# CH592F-3MODE-MS-T0-1v2.net
KiCad netlist of a schematic drawn in Altium Designer
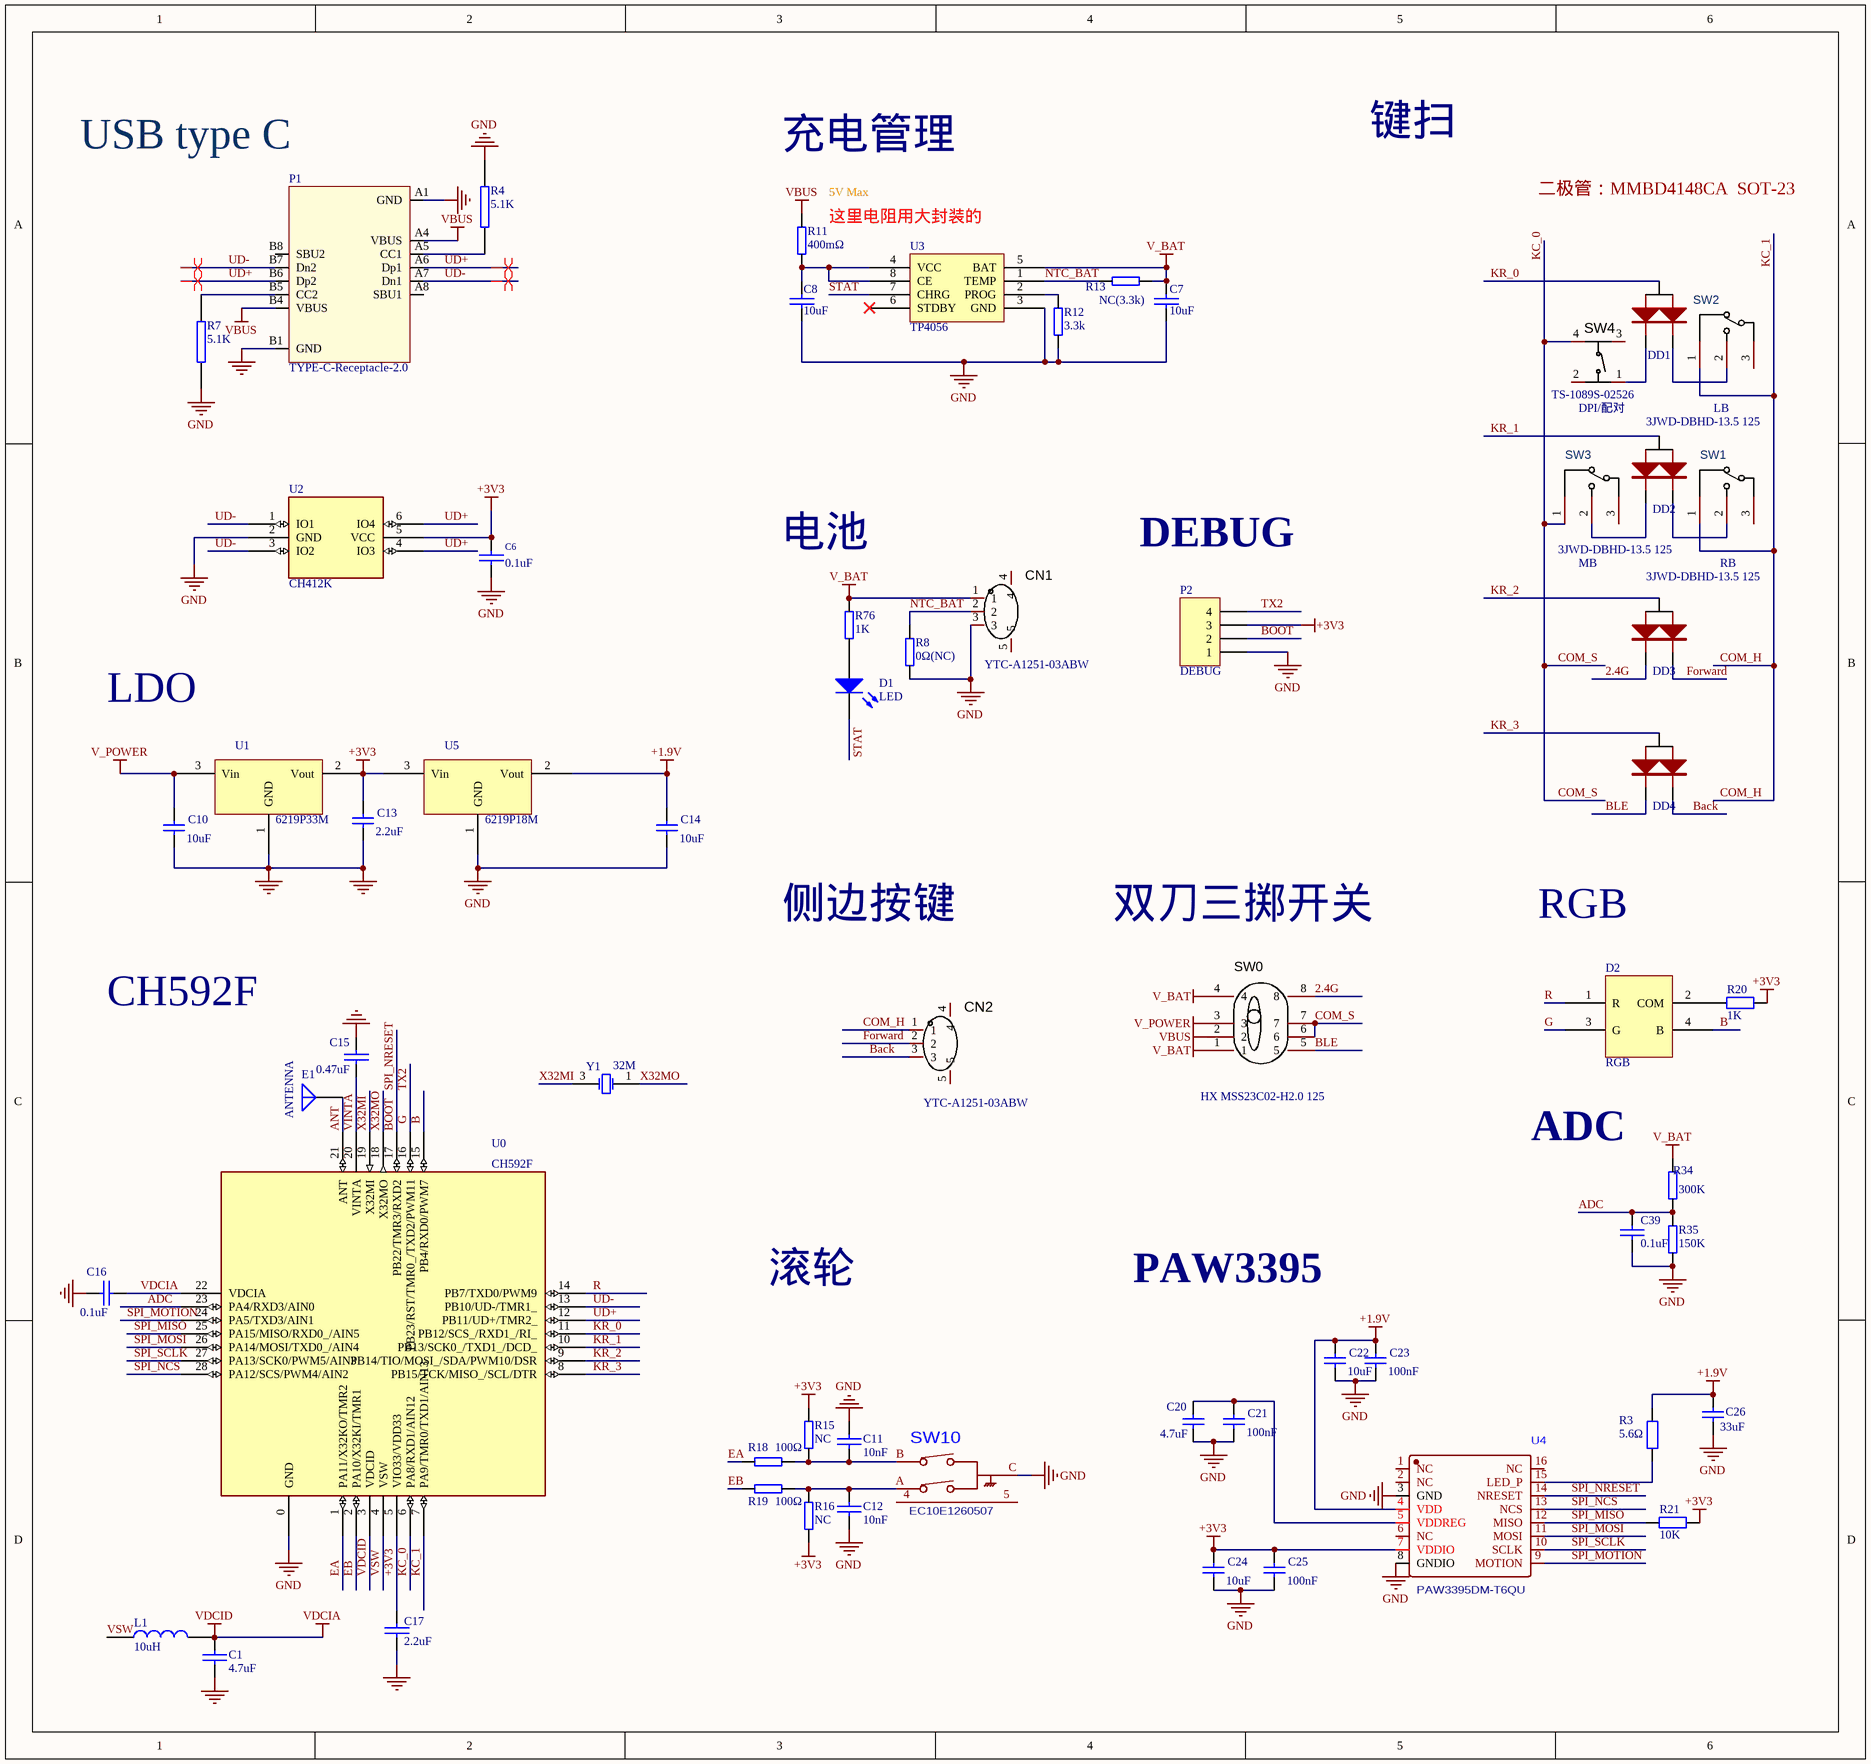
[diagram p0: CH592F-3MODE-MS-T0-1v2.SchDoc]

(export (version "E")
  (design (tool "Eeschema 10.0.6"))
  (components
    (comp (ref "C1")
      (value "4.7uF")
      (footprint "0402_C")
      (description "Capacitor")
      (libsource (lib "") (part "CAP_1"))
    )
    (comp (ref "C6")
      (value "0.1uF")
      (footprint "0402_C")
      (description "Capacitor")
      (libsource (lib "wch_sch_others") (part "CAP"))
    )
    (comp (ref "C7")
      (value "10uF")
      (footprint "0603_C")
      (description "Capacitor")
      (libsource (lib "wch_sch_others") (part "CAP"))
    )
    (comp (ref "C8")
      (value "10uF")
      (footprint "0603_C")
      (description "Capacitor")
      (libsource (lib "wch_sch_others") (part "CAP"))
    )
    (comp (ref "C10")
      (value "10uF")
      (footprint "0603_C")
      (description "Capacitor")
      (fields (field (name "PUBLISHER") "Altium Limited"))
      (libsource (lib "Miscellaneous Devices") (part "Cap"))
    )
    (comp (ref "C11")
      (value "10nF")
      (footprint "0402_C")
      (description "Capacitor")
      (libsource (lib "wch_sch_others(1)") (part "CAP"))
    )
    (comp (ref "C12")
      (value "10nF")
      (footprint "0402_C")
      (description "Capacitor")
      (libsource (lib "wch_sch_others(1)") (part "CAP"))
    )
    (comp (ref "C13")
      (value "2.2uF")
      (footprint "0402_C")
      (description "Capacitor")
      (fields (field (name "PUBLISHER") "Altium Limited"))
      (libsource (lib "Miscellaneous Devices") (part "Cap"))
    )
    (comp (ref "C14")
      (value "10uF")
      (footprint "0603_C")
      (description "Capacitor")
      (fields (field (name "PUBLISHER") "Altium Limited"))
      (libsource (lib "Miscellaneous Devices") (part "Cap"))
    )
    (comp (ref "C15")
      (value "0.47uF")
      (footprint "0402_C")
      (description "Capacitor")
      (libsource (lib "*") (part "CAP"))
    )
    (comp (ref "C16")
      (value "0.1uF")
      (footprint "0402_C")
      (description "Capacitor")
      (libsource (lib "*") (part "CAP"))
    )
    (comp (ref "C17")
      (value "2.2uF")
      (footprint "0402_C")
      (description "Capacitor")
      (libsource (lib "*") (part "CAP"))
    )
    (comp (ref "C20")
      (value "4.7uF")
      (footprint "0402_C")
      (description "Capacitor")
      (fields (field (name "PUBLISHER") "Altium Limited"))
      (libsource (lib "Miscellaneous Devices") (part "Cap"))
    )
    (comp (ref "C21")
      (value "100nF")
      (footprint "0402_C")
      (description "Capacitor")
      (fields (field (name "PUBLISHER") "Altium Limited"))
      (libsource (lib "Miscellaneous Devices") (part "Cap"))
    )
    (comp (ref "C22")
      (value "10uF")
      (footprint "0603_C")
      (description "Capacitor")
      (fields (field (name "PUBLISHER") "Altium Limited"))
      (libsource (lib "Miscellaneous Devices") (part "Cap"))
    )
    (comp (ref "C23")
      (value "100nF")
      (footprint "0402_C")
      (description "Capacitor")
      (fields (field (name "PUBLISHER") "Altium Limited"))
      (libsource (lib "Miscellaneous Devices") (part "Cap"))
    )
    (comp (ref "C24")
      (value "10uF")
      (footprint "0603_C")
      (description "Capacitor")
      (fields (field (name "PUBLISHER") "Altium Limited"))
      (libsource (lib "Miscellaneous Devices") (part "Cap"))
    )
    (comp (ref "C25")
      (value "100nF")
      (footprint "0402_C")
      (description "Capacitor")
      (fields (field (name "PUBLISHER") "Altium Limited"))
      (libsource (lib "Miscellaneous Devices") (part "Cap"))
    )
    (comp (ref "C26")
      (value "33uF")
      (footprint "3528_C")
      (description "Capacitor")
      (fields (field (name "PUBLISHER") "Altium Limited"))
      (libsource (lib "Miscellaneous Devices") (part "Cap"))
    )
    (comp (ref "C39")
      (value "0.1uF")
      (footprint "0402_C")
      (description "Capacitor")
      (libsource (lib "wch_sch_others") (part "CAP"))
    )
    (comp (ref "CN1")
      (value "YTC-A1251-03ABW")
      (footprint "CONN-SMD_3P-P1.25_YTC-A1251-03ABW")
      (fields (field (name "MANUFACTURER") "YIYUAN(怡远)"))
      (libsource (lib "altium-import") (part "root_0_YTC-A1251-03ABW_"))
    )
    (comp (ref "CN2")
      (value "YTC-A1251-03ABW")
      (footprint "CONN-SMD_3P-P1.25_YTC-A1251-03ABW")
      (fields (field (name "MANUFACTURER") "YIYUAN(怡远)"))
      (libsource (lib "altium-import") (part "root_0_YTC-A1251-03ABW_"))
    )
    (comp (ref "D1")
      (value "LED")
      (footprint "0603+")
      (description "Typical INFRARED GaAs LED")
      (fields (field (name "PUBLISHER") "Altium Limited"))
      (libsource (lib "Miscellaneous Devices") (part "LED0"))
    )
    (comp (ref "D2")
      (value "RGB")
      (footprint "RGB")
      (description "共阳")
      (libsource (lib "wch_sch_others") (part "RGB"))
    )
    (comp (ref "DD1")
      (value "DIODE")
      (footprint "CHXXX:SOT-23")
      (description "Diode")
      (libsource (lib "二极管 Copy of CH643U-White-KB-T0-1v0") (part "DIODE"))
    )
    (comp (ref "DD2")
      (value "DIODE")
      (footprint "CHXXX:SOT-23")
      (description "Diode")
      (libsource (lib "二极管 Copy of CH643U-White-KB-T0-1v0") (part "DIODE"))
    )
    (comp (ref "DD3")
      (value "DIODE")
      (footprint "CHXXX:SOT-23")
      (description "Diode")
      (libsource (lib "二极管 Copy of CH643U-White-KB-T0-1v0") (part "DIODE"))
    )
    (comp (ref "DD4")
      (value "DIODE")
      (footprint "CHXXX:SOT-23")
      (description "Diode")
      (libsource (lib "二极管 Copy of CH643U-White-KB-T0-1v0") (part "DIODE"))
    )
    (comp (ref "E1")
      (value "ANTENNA")
      (footprint "ANT-F-1-2.4G-1.0mmFR4")
      (description "Generic Antenna")
      (libsource (lib "*") (part "ANTENNA"))
    )
    (comp (ref "L1") (value "10uH") (footprint "SMD_2x2mm") (libsource (lib "*") (part "INDUCTOR")))
    (comp (ref "P1")
      (value "TYPE-C-Receptacle-2.0")
      (footprint "TYPE-C-Receptacle-2.0-6.5*8.94*3.16-SinkDown")
      (description "Type-C USB2.0 母座")
      (libsource (lib "Miscellaneous SCH Lib") (part "TYPE-C-Receptacle-2.0"))
    )
    (comp (ref "P2")
      (value "DEBUG")
      (footprint "SIP4-2.54mm")
      (description "Header, 4-Pin")
      (fields (field (name "PUBLISHER") "Altium Limited"))
      (libsource (lib "Miscellaneous Connectors") (part "Header 4"))
    )
    (comp (ref "R3")
      (value "5.6Ω")
      (footprint "0402")
      (description "Resistor")
      (fields (field (name "PUBLISHER") "Altium Limited"))
      (libsource (lib "Miscellaneous Devices") (part "Res2"))
    )
    (comp (ref "R4") (value "5.1K") (footprint "0402") (libsource (lib "*") (part "RES2")))
    (comp (ref "R7") (value "5.1K") (footprint "0402") (libsource (lib "*") (part "RES2")))
    (comp (ref "R8") (value "0Ω(NC)") (footprint "0402") (libsource (lib "wch_sch_others") (part "RES")))
    (comp (ref "R11")
      (value "400mΩ")
      (footprint "CHXXX:1206")
      (libsource (lib "wch_sch_others") (part "RES"))
    )
    (comp (ref "R12") (value "3.3k") (footprint "0402") (libsource (lib "wch_sch_others") (part "RES")))
    (comp (ref "R13") (value "NC(3.3k)") (footprint "0402") (libsource (lib "wch_sch_others") (part "RES")))
    (comp (ref "R15") (value "NC") (footprint "0402") (libsource (lib "wch_sch_others") (part "RES")))
    (comp (ref "R16") (value "NC") (footprint "0402") (libsource (lib "wch_sch_others") (part "RES")))
    (comp (ref "R18") (value "100Ω") (footprint "0402") (libsource (lib "wch_sch_others") (part "RES")))
    (comp (ref "R19") (value "100Ω") (footprint "0402") (libsource (lib "wch_sch_others") (part "RES")))
    (comp (ref "R20")
      (value "1K")
      (footprint "0402")
      (description "Resistor")
      (fields (field (name "PUBLISHER") "Altium Limited"))
      (libsource (lib "") (part "Res2_1"))
    )
    (comp (ref "R21")
      (value "10K")
      (footprint "0402")
      (description "Resistor")
      (fields (field (name "PUBLISHER") "Altium Limited"))
      (libsource (lib "") (part "Res2_1"))
    )
    (comp (ref "R34") (value "300K") (footprint "0402") (libsource (lib "wch_sch_others") (part "RES")))
    (comp (ref "R35") (value "150K") (footprint "0402") (libsource (lib "wch_sch_others") (part "RES")))
    (comp (ref "R76") (value "1K") (footprint "0402") (libsource (lib "wch_sch_others") (part "RES")))
    (comp (ref "SW0")
      (value "HX MSS23C02-H2.0 125")
      (footprint "SW-SMD_HX-MSS23C02-H2.0-125")
      (fields (field (name "MANUFACTURER") "hanxia(韩下)"))
      (libsource (lib "altium-import") (part "root_1_HX MSS23C02-H2.0 125_"))
    )
    (comp (ref "SW1")
      (value "3JWD-DBHD-13.5 125")
      (footprint "SW-TH_SHOU-HAN_3JWD-DBHD-13.5")
      (fields (field (name "MANUFACTURER") "SHOU HAN(首韩)"))
      (libsource (lib "altium-import") (part "root_0_3JWD-DBHD-13.5 125_"))
    )
    (comp (ref "SW2")
      (value "3JWD-DBHD-13.5 125")
      (footprint "SW-TH_SHOU-HAN_3JWD-DBHD-13.5")
      (fields (field (name "MANUFACTURER") "SHOU HAN(首韩)"))
      (libsource (lib "altium-import") (part "root_0_3JWD-DBHD-13.5 125_"))
    )
    (comp (ref "SW3")
      (value "3JWD-DBHD-13.5 125")
      (footprint "SW-TH_SHOU-HAN_3JWD-DBHD-13.5")
      (fields (field (name "MANUFACTURER") "SHOU HAN(首韩)"))
      (libsource (lib "altium-import") (part "root_0_3JWD-DBHD-13.5 125_"))
    )
    (comp (ref "SW4")
      (value "TS-1089S-02526")
      (footprint "SW-SMD_4P-L4.2-W3.3-P2.15-LS5.1")
      (fields (field (name "MANUFACTURER") "XUNPU(讯普)"))
      (libsource (lib "altium-import") (part "root_2_TS-1089S-02526_"))
    )
    (comp (ref "SW10")
      (value "EC10E1260507")
      (footprint "SW-TH_EC10EXXXXXXX")
      (libsource (lib "altium-import") (part "root_0_EC10E1260507_"))
    )
    (comp (ref "U0")
      (value "CH592F")
      (footprint "QFN28_4X4")
      (description "RISC-V MCU with BLE/USB/ADC/SPI/4*UART/I2C/LCD")
      (libsource (lib "DHXXXSCH") (part "CH592F"))
    )
    (comp (ref "U1")
      (value "6219P33M")
      (footprint "SOT-23")
      (libsource (lib "wch_sch_others") (part "6219P33M"))
    )
    (comp (ref "U2")
      (value "CH412K")
      (footprint "SOT-363")
      (description "Qaud ESD protect, high speed")
      (libsource (lib "CHXXX") (part "CH412K"))
    )
    (comp (ref "U3") (value "TP4056") (footprint "ESOP8") (libsource (lib "Schlib1") (part "TP4056")))
    (comp (ref "U4")
      (value "PAW3395DM-T6QU")
      (footprint "DIP-16_PAW3395DM-T6QU")
      (libsource (lib "altium-import") (part "root_0_PAW3395DM-T6QU_"))
    )
    (comp (ref "U5")
      (value "6219P18M")
      (footprint "SOT-23")
      (libsource (lib "wch_sch_others") (part "6219P33M"))
    )
    (comp (ref "Y1")
      (value "32M")
      (footprint "XT3225")
      (description "Crystal Oscillator")
      (fields (field (name "PUBLISHER") "Altium Limited"))
      (libsource (lib "*") (part "XTAL"))
    )
  )
  (nets
    (net (code "1") (name "+1.9V") (class "Default")
      (node (ref "C14") (pin "1") (pinfunction "1_1") (pintype "passive"))
      (node (ref "C22") (pin "1") (pinfunction "1_1") (pintype "passive"))
      (node (ref "C23") (pin "1") (pinfunction "1_1") (pintype "passive"))
      (node (ref "C26") (pin "1") (pinfunction "1_1") (pintype "passive"))
      (node (ref "R3") (pin "1") (pinfunction "1_1") (pintype "passive"))
      (node (ref "U4") (pin "4") (pinfunction "VDD_4") (pintype "passive"))
      (node (ref "U5") (pin "2") (pinfunction "Vout_2") (pintype "passive"))
    )
    (net (code "2") (name "+3V3") (class "Default")
      (node (ref "C13") (pin "1") (pinfunction "1_1") (pintype "passive"))
      (node (ref "C17") (pin "2") (pinfunction "2_2") (pintype "passive"))
      (node (ref "C24") (pin "1") (pinfunction "1_1") (pintype "passive"))
      (node (ref "C25") (pin "1") (pinfunction "1_1") (pintype "passive"))
      (node (ref "C6") (pin "2") (pinfunction "2_2") (pintype "passive"))
      (node (ref "P2") (pin "3") (pinfunction "3_3") (pintype "passive"))
      (node (ref "R15") (pin "2") (pintype "passive"))
      (node (ref "R16") (pin "1") (pintype "passive"))
      (node (ref "R20") (pin "1") (pinfunction "1_1") (pintype "passive"))
      (node (ref "R21") (pin "1") (pinfunction "1_1") (pintype "passive"))
      (node (ref "U0") (pin "5") (pinfunction "VIO33/VDD33_5") (pintype "power_in"))
      (node (ref "U1") (pin "2") (pinfunction "Vout_2") (pintype "passive"))
      (node (ref "U2") (pin "5") (pinfunction "VCC_5") (pintype "power_in"))
      (node (ref "U4") (pin "7") (pinfunction "VDDIO_7") (pintype "passive"))
      (node (ref "U5") (pin "3") (pinfunction "Vin_3") (pintype "passive"))
    )
    (net (code "3") (name "/2.4G") (class "Default")
      (node (ref "DD3") (pin "2") (pintype "passive"))
      (node (ref "SW0") (pin "8") (pinfunction "8_8") (pintype "passive"))
    )
    (net (code "4") (name "/ADC") (class "Default")
      (node (ref "C39") (pin "1") (pinfunction "1_1") (pintype "passive"))
      (node (ref "R34") (pin "1") (pintype "passive"))
      (node (ref "R35") (pin "2") (pintype "passive"))
      (node (ref "U0") (pin "23") (pinfunction "PA4/RXD3/AIN0_23") (pintype "bidirectional"))
    )
    (net (code "5") (name "/ANT") (class "Default")
      (node (ref "E1") (pin "1") (pinfunction "A_1") (pintype "passive"))
      (node (ref "U0") (pin "21") (pinfunction "ANT_21") (pintype "bidirectional"))
    )
    (net (code "6") (name "/B") (class "Default")
      (node (ref "D2") (pin "4") (pinfunction "B_4") (pintype "passive"))
      (node (ref "U0") (pin "15") (pinfunction "PB4/RXD0/PWM7_15") (pintype "bidirectional"))
    )
    (net (code "7") (name "/BLE") (class "Default")
      (node (ref "DD4") (pin "2") (pintype "passive"))
      (node (ref "SW0") (pin "5") (pinfunction "5_5") (pintype "passive"))
    )
    (net (code "8") (name "/BOOT") (class "Default")
      (node (ref "P2") (pin "2") (pinfunction "2_2") (pintype "passive"))
      (node (ref "U0") (pin "17") (pinfunction "PB22/TMR3/RXD2_17") (pintype "bidirectional"))
      (node (ref "U4") (pin "14") (pinfunction "NRESET_14") (pintype "passive"))
    )
    (net (code "9") (name "/Back") (class "Default")
      (node (ref "CN2") (pin "3") (pinfunction "3_3") (pintype "passive"))
      (node (ref "DD4") (pin "1") (pintype "passive"))
    )
    (net (code "10") (name "/COM_H") (class "Default")
      (node (ref "CN2") (pin "1") (pinfunction "1_1") (pintype "passive"))
      (node (ref "SW1") (pin "1") (pinfunction "C_1") (pintype "passive"))
      (node (ref "SW2") (pin "1") (pinfunction "C_1") (pintype "passive"))
      (node (ref "U0") (pin "7") (pinfunction "PA9/TMR0/TXD1/AIN13_7") (pintype "bidirectional"))
    )
    (net (code "11") (name "/COM_S") (class "Default")
      (node (ref "SW0") (pin "6") (pinfunction "6_6") (pintype "passive"))
      (node (ref "SW0") (pin "7") (pinfunction "7_7") (pintype "passive"))
      (node (ref "SW3") (pin "1") (pinfunction "C_1") (pintype "passive"))
      (node (ref "SW4") (pin "4") (pinfunction "4_4") (pintype "passive"))
      (node (ref "U0") (pin "6") (pinfunction "PA8/RXD1/AIN12_6") (pintype "bidirectional"))
    )
    (net (code "12") (name "/EA") (class "Default")
      (node (ref "R18") (pin "2") (pintype "passive"))
      (node (ref "U0") (pin "1") (pinfunction "PA11/X32KO/TMR2_1") (pintype "bidirectional"))
    )
    (net (code "13") (name "/EB") (class "Default")
      (node (ref "R19") (pin "1") (pintype "passive"))
      (node (ref "U0") (pin "2") (pinfunction "PA10/X32KI/TMR1_2") (pintype "bidirectional"))
    )
    (net (code "14") (name "/Forward") (class "Default")
      (node (ref "CN2") (pin "2") (pinfunction "2_2") (pintype "passive"))
      (node (ref "DD3") (pin "1") (pintype "passive"))
    )
    (net (code "15") (name "/G") (class "Default")
      (node (ref "D2") (pin "3") (pinfunction "G_3") (pintype "passive"))
      (node (ref "P2") (pin "4") (pinfunction "4_4") (pintype "passive"))
      (node (ref "U0") (pin "16") (pinfunction "PB23/RST/TMR0_/TXD2/PWM11_16") (pintype "bidirectional"))
    )
    (net (code "16") (name "/KR_0") (class "Default")
      (node (ref "DD1") (pin "3") (pintype "passive"))
      (node (ref "U0") (pin "11") (pinfunction "PB12/SCS_/RXD1_/RI__11") (pintype "bidirectional"))
    )
    (net (code "17") (name "/KR_1") (class "Default")
      (node (ref "DD2") (pin "3") (pintype "passive"))
      (node (ref "U0") (pin "10") (pinfunction "PB13/SCK0_/TXD1_/DCD__10") (pintype "bidirectional"))
    )
    (net (code "18") (name "/KR_2") (class "Default")
      (node (ref "DD3") (pin "3") (pintype "passive"))
      (node (ref "U0") (pin "9") (pinfunction "PB14/TIO/MOSI_/SDA/PWM10/DSR_9") (pintype "bidirectional"))
    )
    (net (code "19") (name "/KR_3") (class "Default")
      (node (ref "DD4") (pin "3") (pintype "passive"))
      (node (ref "U0") (pin "8") (pinfunction "PB15/TCK/MISO_/SCL/DTR_8") (pintype "bidirectional"))
    )
    (net (code "20") (name "/NTC_BAT") (class "Default")
      (node (ref "CN1") (pin "2") (pinfunction "2_2") (pintype "passive"))
      (node (ref "R13") (pin "2") (pintype "passive"))
      (node (ref "R8") (pin "1") (pintype "passive"))
      (node (ref "U3") (pin "1") (pinfunction "TEMP_1") (pintype "passive"))
    )
    (net (code "21") (name "/R") (class "Default")
      (node (ref "D2") (pin "1") (pinfunction "R_1") (pintype "passive"))
      (node (ref "U0") (pin "14") (pinfunction "PB7/TXD0/PWM9_14") (pintype "bidirectional"))
    )
    (net (code "22") (name "/SPI_MISO") (class "Default")
      (node (ref "R21") (pin "2") (pinfunction "2_2") (pintype "passive"))
      (node (ref "U0") (pin "25") (pinfunction "PA15/MISO/RXD0_/AIN5_25") (pintype "bidirectional"))
      (node (ref "U4") (pin "12") (pinfunction "MISO_12") (pintype "passive"))
    )
    (net (code "23") (name "/SPI_MOSI") (class "Default")
      (node (ref "U0") (pin "26") (pinfunction "PA14/MOSI/TXD0_/AIN4_26") (pintype "bidirectional"))
      (node (ref "U4") (pin "11") (pinfunction "MOSI_11") (pintype "passive"))
    )
    (net (code "24") (name "/SPI_MOTION") (class "Default")
      (node (ref "U0") (pin "24") (pinfunction "PA5/TXD3/AIN1_24") (pintype "bidirectional"))
      (node (ref "U4") (pin "9") (pinfunction "MOTION_9") (pintype "passive"))
    )
    (net (code "25") (name "/SPI_NCS") (class "Default")
      (node (ref "U0") (pin "28") (pinfunction "PA12/SCS/PWM4/AIN2_28") (pintype "bidirectional"))
      (node (ref "U4") (pin "13") (pinfunction "NCS_13") (pintype "passive"))
    )
    (net (code "26") (name "/SPI_SCLK") (class "Default")
      (node (ref "U0") (pin "27") (pinfunction "PA13/SCK0/PWM5/AIN3_27") (pintype "bidirectional"))
      (node (ref "U4") (pin "10") (pinfunction "SCLK_10") (pintype "passive"))
    )
    (net (code "27") (name "/STAT") (class "Default")
      (node (ref "D1") (pin "2") (pinfunction "K_2") (pintype "passive"))
      (node (ref "U3") (pin "7") (pinfunction "CHRG_7") (pintype "passive"))
    )
    (net (code "28") (name "/UD+") (class "Default")
      (node (ref "P1") (pin "A6") (pinfunction "Dp1_A6") (pintype "passive"))
      (node (ref "P1") (pin "B6") (pinfunction "Dp2_B6") (pintype "passive"))
      (node (ref "U0") (pin "12") (pinfunction "PB11/UD+/TMR2__12") (pintype "bidirectional"))
      (node (ref "U2") (pin "4") (pinfunction "IO3_4") (pintype "bidirectional"))
      (node (ref "U2") (pin "6") (pinfunction "IO4_6") (pintype "bidirectional"))
    )
    (net (code "29") (name "/UD-") (class "Default")
      (node (ref "P1") (pin "A7") (pinfunction "Dn1_A7") (pintype "passive"))
      (node (ref "P1") (pin "B7") (pinfunction "Dn2_B7") (pintype "passive"))
      (node (ref "U0") (pin "13") (pinfunction "PB10/UD-/TMR1__13") (pintype "bidirectional"))
      (node (ref "U2") (pin "1") (pinfunction "IO1_1") (pintype "bidirectional"))
      (node (ref "U2") (pin "3") (pinfunction "IO2_3") (pintype "bidirectional"))
    )
    (net (code "30") (name "/VINTA") (class "Default")
      (node (ref "C15") (pin "1") (pinfunction "1_1") (pintype "passive"))
      (node (ref "U0") (pin "20") (pinfunction "VINTA_20") (pintype "power_in"))
    )
    (net (code "31") (name "/VSW") (class "Default")
      (node (ref "L1") (pin "1") (pinfunction "1_1") (pintype "passive"))
      (node (ref "U0") (pin "4") (pinfunction "VSW_4") (pintype "power_in"))
    )
    (net (code "32") (name "/X32MI") (class "Default")
      (node (ref "U0") (pin "19") (pinfunction "X32MI_19") (pintype "input"))
      (node (ref "Y1") (pin "3") (pinfunction "OSC2_3") (pintype "passive"))
    )
    (net (code "33") (name "/X32MO") (class "Default")
      (node (ref "U0") (pin "18") (pinfunction "X32MO_18") (pintype "output"))
      (node (ref "Y1") (pin "1") (pinfunction "OSC1_1") (pintype "passive"))
    )
    (net (code "34") (name "GND") (class "Default")
      (node (ref "C1") (pin "1") (pinfunction "1_1") (pintype "passive"))
      (node (ref "C10") (pin "2") (pinfunction "2_2") (pintype "passive"))
      (node (ref "C11") (pin "1") (pinfunction "1_1") (pintype "passive"))
      (node (ref "C12") (pin "1") (pinfunction "1_1") (pintype "passive"))
      (node (ref "C13") (pin "2") (pinfunction "2_2") (pintype "passive"))
      (node (ref "C14") (pin "2") (pinfunction "2_2") (pintype "passive"))
      (node (ref "C15") (pin "2") (pinfunction "2_2") (pintype "passive"))
      (node (ref "C16") (pin "2") (pinfunction "2_2") (pintype "passive"))
      (node (ref "C17") (pin "1") (pinfunction "1_1") (pintype "passive"))
      (node (ref "C20") (pin "2") (pinfunction "2_2") (pintype "passive"))
      (node (ref "C21") (pin "2") (pinfunction "2_2") (pintype "passive"))
      (node (ref "C22") (pin "2") (pinfunction "2_2") (pintype "passive"))
      (node (ref "C23") (pin "2") (pinfunction "2_2") (pintype "passive"))
      (node (ref "C24") (pin "2") (pinfunction "2_2") (pintype "passive"))
      (node (ref "C25") (pin "2") (pinfunction "2_2") (pintype "passive"))
      (node (ref "C26") (pin "2") (pinfunction "2_2") (pintype "passive"))
      (node (ref "C39") (pin "2") (pinfunction "2_2") (pintype "passive"))
      (node (ref "C6") (pin "1") (pinfunction "1_1") (pintype "passive"))
      (node (ref "C7") (pin "2") (pinfunction "2_2") (pintype "passive"))
      (node (ref "C8") (pin "2") (pinfunction "2_2") (pintype "passive"))
      (node (ref "CN1") (pin "3") (pinfunction "3_3") (pintype "passive"))
      (node (ref "P1") (pin "A1") (pinfunction "GND_A1") (pintype "passive"))
      (node (ref "P1") (pin "B1") (pinfunction "GND_B1") (pintype "passive"))
      (node (ref "P2") (pin "1") (pinfunction "1_1") (pintype "passive"))
      (node (ref "R12") (pin "2") (pintype "passive"))
      (node (ref "R35") (pin "1") (pintype "passive"))
      (node (ref "R4") (pin "2") (pinfunction "2_2") (pintype "passive"))
      (node (ref "R7") (pin "1") (pinfunction "1_1") (pintype "passive"))
      (node (ref "R8") (pin "2") (pintype "passive"))
      (node (ref "SW10") (pin "C") (pinfunction "C_C") (pintype "passive"))
      (node (ref "U0") (pin "0") (pinfunction "GND_0") (pintype "power_in"))
      (node (ref "U1") (pin "1") (pinfunction "GND_1") (pintype "passive"))
      (node (ref "U2") (pin "2") (pinfunction "GND_2") (pintype "power_in"))
      (node (ref "U3") (pin "3") (pinfunction "GND_3") (pintype "passive"))
      (node (ref "U4") (pin "3") (pinfunction "GND_3") (pintype "passive"))
      (node (ref "U4") (pin "8") (pinfunction "GNDIO_8") (pintype "passive"))
      (node (ref "U5") (pin "1") (pinfunction "GND_1") (pintype "passive"))
    )
    (net (code "35") (name "Net-(C11-Pad2)") (class "Default")
      (node (ref "C11") (pin "2") (pinfunction "2_2") (pintype "passive"))
      (node (ref "R15") (pin "1") (pintype "passive"))
      (node (ref "R18") (pin "1") (pintype "passive"))
      (node (ref "SW10") (pin "B") (pinfunction "B_B") (pintype "passive"))
    )
    (net (code "36") (name "Net-(C12-Pad2)") (class "Default")
      (node (ref "C12") (pin "2") (pinfunction "2_2") (pintype "passive"))
      (node (ref "R16") (pin "2") (pintype "passive"))
      (node (ref "R19") (pin "2") (pintype "passive"))
      (node (ref "SW10") (pin "A") (pinfunction "A_A") (pintype "passive"))
    )
    (net (code "37") (name "Net-(D1-A)") (class "Default")
      (node (ref "D1") (pin "1") (pinfunction "A_1") (pintype "passive"))
      (node (ref "R76") (pin "1") (pintype "passive"))
    )
    (net (code "38") (name "Net-(D2-COM)") (class "Default")
      (node (ref "D2") (pin "2") (pinfunction "COM_2") (pintype "passive"))
      (node (ref "R20") (pin "2") (pinfunction "2_2") (pintype "passive"))
    )
    (net (code "39") (name "Net-(DD1-Pad2)") (class "Default")
      (node (ref "DD1") (pin "2") (pintype "passive"))
      (node (ref "SW4") (pin "1") (pinfunction "1_1") (pintype "passive"))
    )
    (net (code "40") (name "Net-(P1-CC1)") (class "Default")
      (node (ref "P1") (pin "A5") (pinfunction "CC1_A5") (pintype "passive"))
      (node (ref "R4") (pin "1") (pinfunction "1_1") (pintype "passive"))
    )
    (net (code "41") (name "Net-(P1-CC2)") (class "Default")
      (node (ref "P1") (pin "B5") (pinfunction "CC2_B5") (pintype "passive"))
      (node (ref "R7") (pin "2") (pinfunction "2_2") (pintype "passive"))
    )
    (net (code "42") (name "Net-(SW1-ON)") (class "Default")
      (node (ref "DD2") (pin "1") (pintype "passive"))
      (node (ref "SW1") (pin "2") (pinfunction "ON_2") (pintype "passive"))
    )
    (net (code "43") (name "Net-(SW2-ON)") (class "Default")
      (node (ref "DD1") (pin "1") (pintype "passive"))
      (node (ref "SW2") (pin "2") (pinfunction "ON_2") (pintype "passive"))
    )
    (net (code "44") (name "Net-(SW3-ON)") (class "Default")
      (node (ref "DD2") (pin "2") (pintype "passive"))
      (node (ref "SW3") (pin "2") (pinfunction "ON_2") (pintype "passive"))
    )
    (net (code "45") (name "Net-(U3-CE)") (class "Default")
      (node (ref "C8") (pin "1") (pinfunction "1_1") (pintype "passive"))
      (node (ref "R11") (pin "2") (pintype "passive"))
      (node (ref "U3") (pin "4") (pinfunction "VCC_4") (pintype "passive"))
      (node (ref "U3") (pin "8") (pinfunction "CE_8") (pintype "passive"))
    )
    (net (code "46") (name "Net-(U3-PROG)") (class "Default")
      (node (ref "R12") (pin "1") (pintype "passive"))
      (node (ref "U3") (pin "2") (pinfunction "PROG_2") (pintype "passive"))
    )
    (net (code "47") (name "Net-(U4-LED_P)") (class "Default")
      (node (ref "R3") (pin "2") (pinfunction "2_2") (pintype "passive"))
      (node (ref "U4") (pin "15") (pinfunction "LED_P_15") (pintype "passive"))
    )
    (net (code "48") (name "Net-(U4-VDDREG)") (class "Default")
      (node (ref "C20") (pin "1") (pinfunction "1_1") (pintype "passive"))
      (node (ref "C21") (pin "1") (pinfunction "1_1") (pintype "passive"))
      (node (ref "U4") (pin "5") (pinfunction "VDDREG_5") (pintype "passive"))
    )
    (net (code "49") (name "VBUS") (class "Default")
      (node (ref "P1") (pin "A4") (pinfunction "VBUS_A4") (pintype "passive"))
      (node (ref "P1") (pin "B4") (pinfunction "VBUS_B4") (pintype "passive"))
      (node (ref "R11") (pin "1") (pintype "passive"))
      (node (ref "SW0") (pin "2") (pinfunction "2_2") (pintype "passive"))
    )
    (net (code "50") (name "VDCIA") (class "Default")
      (node (ref "C1") (pin "2") (pinfunction "2_2") (pintype "passive"))
      (node (ref "C16") (pin "1") (pinfunction "1_1") (pintype "passive"))
      (node (ref "L1") (pin "2") (pinfunction "2_2") (pintype "passive"))
      (node (ref "U0") (pin "22") (pinfunction "VDCIA_22") (pintype "power_in"))
      (node (ref "U0") (pin "3") (pinfunction "VDCID_3") (pintype "power_in"))
    )
    (net (code "51") (name "V_BAT") (class "Default")
      (node (ref "C7") (pin "1") (pinfunction "1_1") (pintype "passive"))
      (node (ref "CN1") (pin "1") (pinfunction "1_1") (pintype "passive"))
      (node (ref "R13") (pin "1") (pintype "passive"))
      (node (ref "R34") (pin "2") (pintype "passive"))
      (node (ref "R76") (pin "2") (pintype "passive"))
      (node (ref "SW0") (pin "1") (pinfunction "1_1") (pintype "passive"))
      (node (ref "SW0") (pin "4") (pinfunction "4_4") (pintype "passive"))
      (node (ref "U3") (pin "5") (pinfunction "BAT_5") (pintype "passive"))
    )
    (net (code "52") (name "V_POWER") (class "Default")
      (node (ref "C10") (pin "1") (pinfunction "1_1") (pintype "passive"))
      (node (ref "SW0") (pin "3") (pinfunction "3_3") (pintype "passive"))
      (node (ref "U1") (pin "3") (pinfunction "Vin_3") (pintype "passive"))
    )
    (net (code "53") (name "unconnected-(CN1-Pad4)") (class "Default")
      (node (ref "CN1") (pin "4") (pinfunction "4_4") (pintype "passive"))
    )
    (net (code "54") (name "unconnected-(CN1-Pad5)") (class "Default")
      (node (ref "CN1") (pin "5") (pinfunction "5_5") (pintype "passive"))
    )
    (net (code "55") (name "unconnected-(CN2-Pad4)") (class "Default")
      (node (ref "CN2") (pin "4") (pinfunction "4_4") (pintype "passive"))
    )
    (net (code "56") (name "unconnected-(CN2-Pad5)") (class "Default")
      (node (ref "CN2") (pin "5") (pinfunction "5_5") (pintype "passive"))
    )
    (net (code "57") (name "unconnected-(P1-SBU1-PadA8)") (class "Default")
      (node (ref "P1") (pin "A8") (pinfunction "SBU1_A8") (pintype "passive"))
    )
    (net (code "58") (name "unconnected-(P1-SBU2-PadB8)") (class "Default")
      (node (ref "P1") (pin "B8") (pinfunction "SBU2_B8") (pintype "passive"))
    )
    (net (code "59") (name "unconnected-(SW1-NC-Pad3)") (class "Default")
      (node (ref "SW1") (pin "3") (pinfunction "NC_3") (pintype "passive"))
    )
    (net (code "60") (name "unconnected-(SW2-NC-Pad3)") (class "Default")
      (node (ref "SW2") (pin "3") (pinfunction "NC_3") (pintype "passive"))
    )
    (net (code "61") (name "unconnected-(SW3-NC-Pad3)") (class "Default")
      (node (ref "SW3") (pin "3") (pinfunction "NC_3") (pintype "passive"))
    )
    (net (code "62") (name "unconnected-(SW4-Pad2)") (class "Default")
      (node (ref "SW4") (pin "2") (pinfunction "2_2") (pintype "passive"))
    )
    (net (code "63") (name "unconnected-(SW4-Pad3)") (class "Default")
      (node (ref "SW4") (pin "3") (pinfunction "3_3") (pintype "passive"))
    )
    (net (code "64") (name "unconnected-(SW10-Pad4)") (class "Default")
      (node (ref "SW10") (pin "4") (pinfunction "4_4") (pintype "passive"))
    )
    (net (code "65") (name "unconnected-(SW10-Pad5)") (class "Default")
      (node (ref "SW10") (pin "5") (pinfunction "5_5") (pintype "passive"))
    )
    (net (code "66") (name "unconnected-(U3-STDBY-Pad6)") (class "Default")
      (node (ref "U3") (pin "6") (pinfunction "STDBY_6") (pintype "passive+no_connect"))
    )
    (net (code "67") (name "unconnected-(U4-NC-Pad1)") (class "Default")
      (node (ref "U4") (pin "1") (pinfunction "NC_1") (pintype "passive"))
    )
    (net (code "68") (name "unconnected-(U4-NC-Pad2)") (class "Default")
      (node (ref "U4") (pin "2") (pinfunction "NC_2") (pintype "passive"))
    )
    (net (code "69") (name "unconnected-(U4-NC-Pad6)") (class "Default")
      (node (ref "U4") (pin "6") (pinfunction "NC_6") (pintype "passive"))
    )
    (net (code "70") (name "unconnected-(U4-NC-Pad16)") (class "Default")
      (node (ref "U4") (pin "16") (pinfunction "NC_16") (pintype "passive"))
    )
  )
)
